# MSPBOIADV.net
KiCad netlist of a schematic drawn in EAGLE
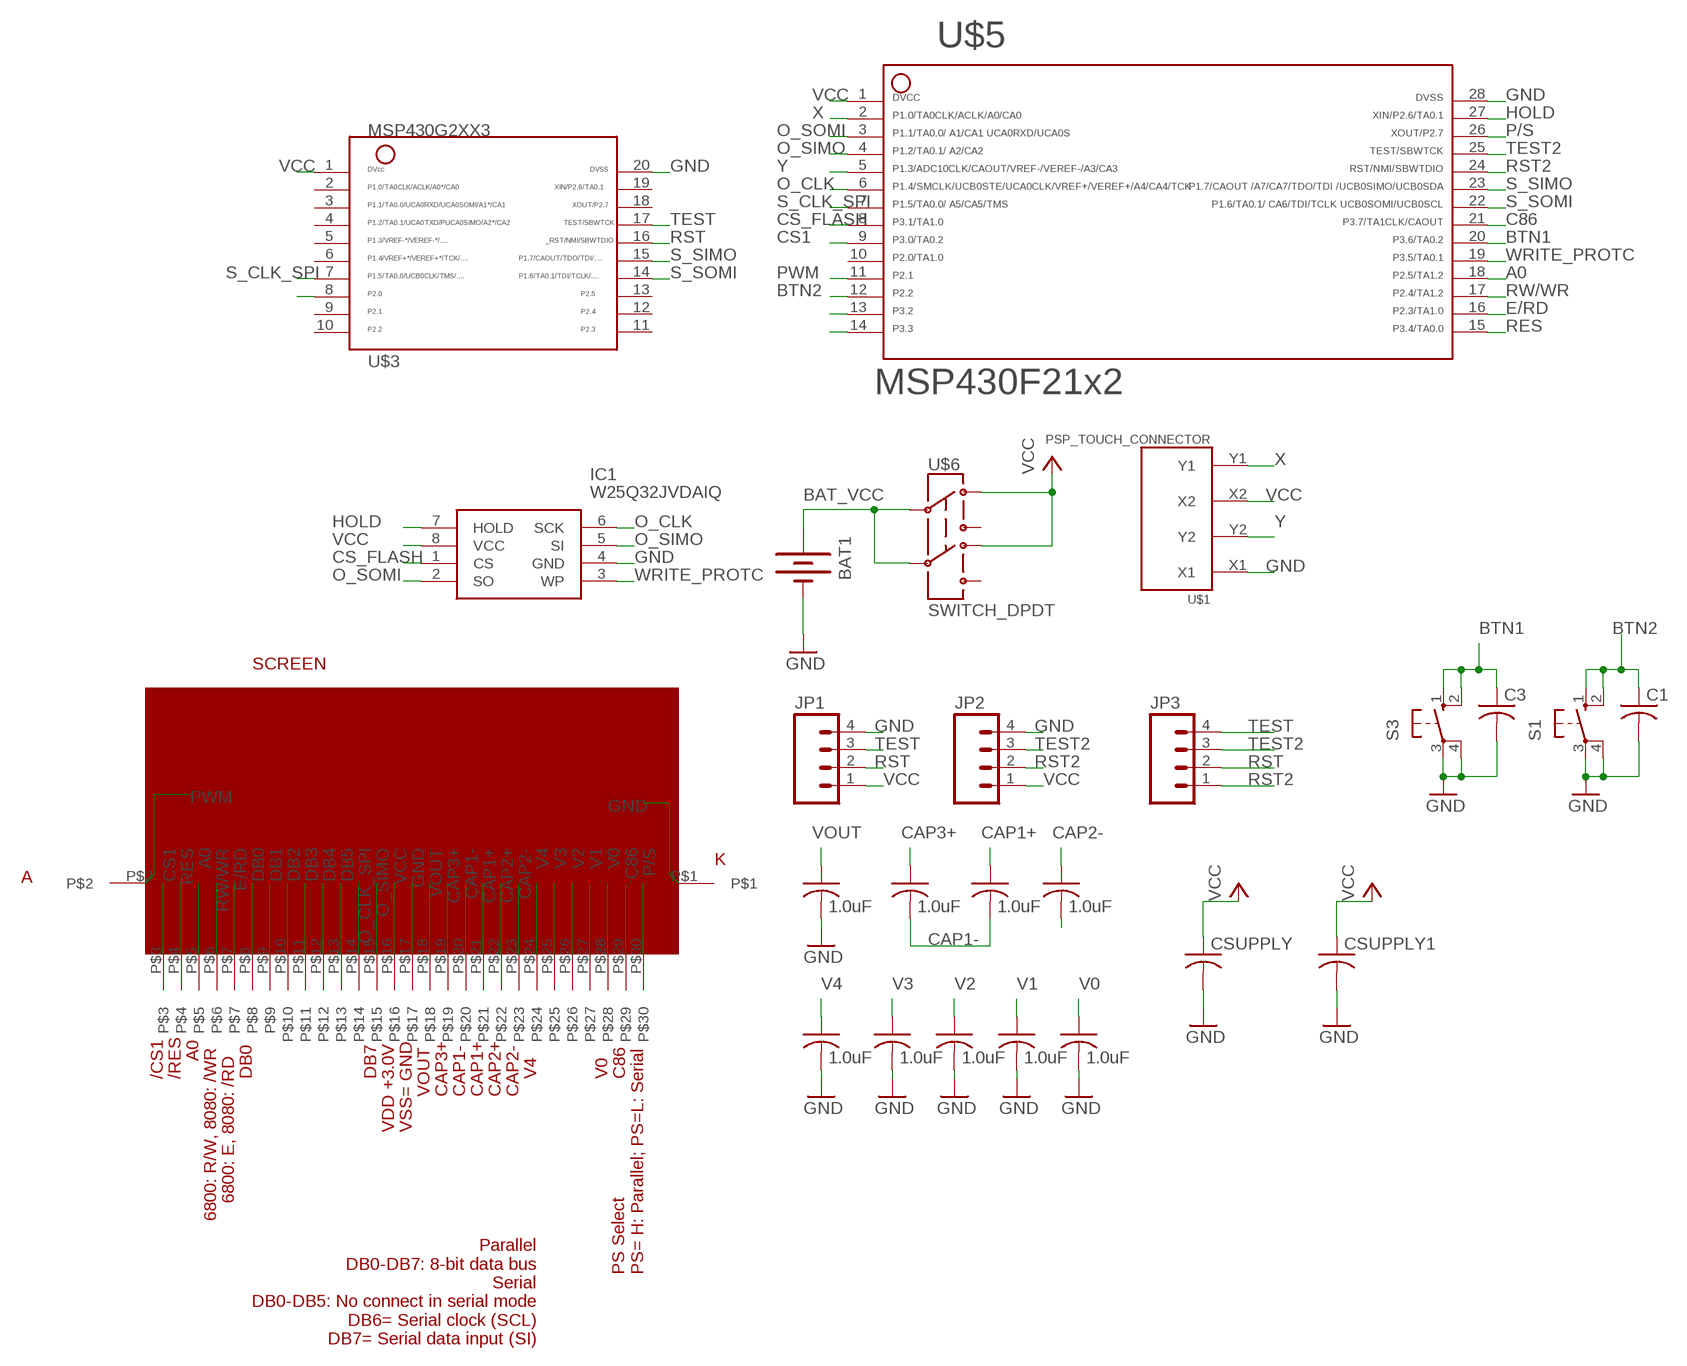
[diagram p0: schematic, sheet 1]

(export (version "E")
  (design (tool "Eeschema 10.0.6"))
  (components
    (comp (ref "1.0UF")
      (value "1.0uF")
      (footprint "eagle-import:C1206")
      (libsource (lib "eagle-import") (part "rcl_334_C-USC1206"))
    )
    (comp (ref "1.0UF1")
      (value "1.0uF")
      (footprint "eagle-import:C1206")
      (libsource (lib "eagle-import") (part "rcl_334_C-USC1206"))
    )
    (comp (ref "BAT1")
      (value "BATTERY")
      (footprint "eagle-import:BATTERY_PACK_2AA")
      (libsource (lib "eagle-import") (part "BATTERY"))
    )
    (comp (ref "C1")
      (value "C-USC1206")
      (footprint "eagle-import:C1206")
      (libsource (lib "eagle-import") (part "rcl_334_C-USC1206"))
    )
    (comp (ref "C3")
      (value "C-USC1206")
      (footprint "eagle-import:C1206")
      (libsource (lib "eagle-import") (part "rcl_334_C-USC1206"))
    )
    (comp (ref "CSUPPLY")
      (value "C-USC1206")
      (footprint "eagle-import:C1206")
      (libsource (lib "eagle-import") (part "C-USC1206"))
    )
    (comp (ref "CSUPPLY1")
      (value "C-USC1206")
      (footprint "eagle-import:C1206")
      (libsource (lib "eagle-import") (part "C-USC1206"))
    )
    (comp (ref "IC1")
      (value "W25Q32JVDAIQ")
      (footprint "eagle-import:DIP902W46P254L959H533Q8N")
      (libsource (lib "eagle-import") (part "W25Q32JVDAIQ"))
    )
    (comp (ref "JP1")
      (value "M04LOCK")
      (footprint "eagle-import:1X04_LOCK")
      (libsource (lib "eagle-import") (part "M04LOCK"))
    )
    (comp (ref "JP2")
      (value "M04LOCK")
      (footprint "eagle-import:1X04_LOCK")
      (libsource (lib "eagle-import") (part "M04LOCK"))
    )
    (comp (ref "JP3")
      (value "M04LOCK")
      (footprint "eagle-import:1X04_LOCK")
      (libsource (lib "eagle-import") (part "M04LOCK"))
    )
    (comp (ref "S1")
      (value "10-XX")
      (footprint "eagle-import:B3F-10XX")
      (fields (field (name "MPN") "B3F-1000"))
      (libsource (lib "eagle-import") (part "10-XX"))
    )
    (comp (ref "S3")
      (value "10-XX")
      (footprint "eagle-import:B3F-10XX")
      (fields (field (name "MPN") "B3F-1000"))
      (libsource (lib "eagle-import") (part "10-XX"))
    )
    (comp (ref "U$1")
      (value "PSP_TOUCH_CONNECTOR")
      (footprint "eagle-import:PSP_TOUCH_CONNECTOR")
      (libsource (lib "eagle-import") (part "PSP_TOUCH_CONNECTOR"))
    )
    (comp (ref "U$2")
      (value "SCREEN")
      (footprint "eagle-import:DISPLAY_128_64")
      (libsource (lib "eagle-import") (part "SCREEN"))
    )
    (comp (ref "U$3")
      (value "MSP430G2XX3TSSOP")
      (footprint "eagle-import:PW20")
      (libsource (lib "eagle-import") (part "MSP430G2XX3TSSOP"))
    )
    (comp (ref "U$5")
      (value "USETHIS")
      (footprint "eagle-import:PW28")
      (libsource (lib "eagle-import") (part "USETHIS"))
    )
    (comp (ref "U$6")
      (value "SWITCH_DPDT")
      (footprint "eagle-import:JS_DPDT_TH")
      (libsource (lib "eagle-import") (part "SWITCH_DPDT"))
    )
    (comp (ref "VOUTCAP")
      (value "1.0uF")
      (footprint "eagle-import:C1206")
      (libsource (lib "eagle-import") (part "rcl_334_C-USC1206"))
    )
    (comp (ref "VOUTCAP1")
      (value "1.0uF")
      (footprint "eagle-import:C1206")
      (libsource (lib "eagle-import") (part "rcl_334_C-USC1206"))
    )
    (comp (ref "VOUTCAP2")
      (value "1.0uF")
      (footprint "eagle-import:C1206")
      (libsource (lib "eagle-import") (part "rcl_334_C-USC1206"))
    )
    (comp (ref "VOUTCAP3")
      (value "1.0uF")
      (footprint "eagle-import:C1206")
      (libsource (lib "eagle-import") (part "rcl_334_C-USC1206"))
    )
    (comp (ref "VOUTCAP4")
      (value "1.0uF")
      (footprint "eagle-import:C1206")
      (libsource (lib "eagle-import") (part "rcl_334_C-USC1206"))
    )
    (comp (ref "VOUTCAP5")
      (value "1.0uF")
      (footprint "eagle-import:C1206")
      (libsource (lib "eagle-import") (part "rcl_334_C-USC1206"))
    )
    (comp (ref "VOUTCAP6")
      (value "1.0uF")
      (footprint "eagle-import:C1206")
      (libsource (lib "eagle-import") (part "rcl_334_C-USC1206"))
    )
  )
  (nets
    (net (code "1") (name "/A0") (class "Default")
      (node (ref "U$2") (pin "P$5") (pinfunction "P$5_P$5") (pintype "bidirectional"))
      (node (ref "U$5") (pin "18") (pinfunction "18_18") (pintype "bidirectional"))
    )
    (net (code "2") (name "/BAT_VCC") (class "Default")
      (node (ref "BAT1") (pin "3V") (pinfunction "+_3V") (pintype "power_in"))
      (node (ref "U$6") (pin "2") (pinfunction "2_2") (pintype "bidirectional"))
      (node (ref "U$6") (pin "5") (pinfunction "5_5") (pintype "bidirectional"))
    )
    (net (code "3") (name "/BTN1") (class "Default")
      (node (ref "C3") (pin "1") (pinfunction "1_1") (pintype "passive"))
      (node (ref "S3") (pin "1") (pinfunction "S_1") (pintype "passive"))
      (node (ref "S3") (pin "2") (pinfunction "S1_2") (pintype "passive"))
      (node (ref "U$5") (pin "20") (pinfunction "20_20") (pintype "bidirectional"))
    )
    (net (code "4") (name "/BTN2") (class "Default")
      (node (ref "C1") (pin "1") (pinfunction "1_1") (pintype "passive"))
      (node (ref "S1") (pin "1") (pinfunction "S_1") (pintype "passive"))
      (node (ref "S1") (pin "2") (pinfunction "S1_2") (pintype "passive"))
      (node (ref "U$5") (pin "12") (pinfunction "12_12") (pintype "bidirectional"))
    )
    (net (code "5") (name "/C86") (class "Default")
      (node (ref "U$2") (pin "P$29") (pinfunction "P$29_P$29") (pintype "bidirectional"))
      (node (ref "U$5") (pin "21") (pinfunction "21_21") (pintype "bidirectional"))
    )
    (net (code "6") (name "/CAP1+") (class "Default")
      (node (ref "1.0UF1") (pin "1") (pinfunction "1_1") (pintype "passive"))
      (node (ref "U$2") (pin "P$21") (pinfunction "P$21_P$21") (pintype "bidirectional"))
    )
    (net (code "7") (name "/CAP1-") (class "Default")
      (node (ref "1.0UF") (pin "2") (pinfunction "2_2") (pintype "passive"))
      (node (ref "1.0UF1") (pin "2") (pinfunction "2_2") (pintype "passive"))
      (node (ref "U$2") (pin "P$20") (pinfunction "P$20_P$20") (pintype "bidirectional"))
    )
    (net (code "8") (name "/CAP2+") (class "Default")
      (node (ref "U$2") (pin "P$22") (pinfunction "P$22_P$22") (pintype "bidirectional"))
      (node (ref "VOUTCAP1") (pin "2") (pinfunction "2_2") (pintype "passive"))
    )
    (net (code "9") (name "/CAP2-") (class "Default")
      (node (ref "U$2") (pin "P$23") (pinfunction "P$23_P$23") (pintype "bidirectional"))
      (node (ref "VOUTCAP1") (pin "1") (pinfunction "1_1") (pintype "passive"))
    )
    (net (code "10") (name "/CAP3+") (class "Default")
      (node (ref "1.0UF") (pin "1") (pinfunction "1_1") (pintype "passive"))
      (node (ref "U$2") (pin "P$19") (pinfunction "P$19_P$19") (pintype "bidirectional"))
    )
    (net (code "11") (name "/CS1") (class "Default")
      (node (ref "U$2") (pin "P$3") (pinfunction "P$3_P$3") (pintype "bidirectional"))
      (node (ref "U$5") (pin "9") (pinfunction "9_9") (pintype "bidirectional"))
    )
    (net (code "12") (name "/CS_FLASH") (class "Default")
      (node (ref "IC1") (pin "1") (pinfunction "CS_1") (pintype "bidirectional"))
      (node (ref "U$5") (pin "8") (pinfunction "8_8") (pintype "bidirectional"))
    )
    (net (code "13") (name "/DB0") (class "Default")
      (node (ref "U$2") (pin "P$8") (pinfunction "P$8_P$8") (pintype "bidirectional"))
    )
    (net (code "14") (name "/DB1") (class "Default")
      (node (ref "U$2") (pin "P$9") (pinfunction "P$9_P$9") (pintype "bidirectional"))
    )
    (net (code "15") (name "/DB2") (class "Default")
      (node (ref "U$2") (pin "P$10") (pinfunction "P$10_P$10") (pintype "bidirectional"))
    )
    (net (code "16") (name "/DB3") (class "Default")
      (node (ref "U$2") (pin "P$11") (pinfunction "P$11_P$11") (pintype "bidirectional"))
    )
    (net (code "17") (name "/DB4") (class "Default")
      (node (ref "U$2") (pin "P$12") (pinfunction "P$12_P$12") (pintype "bidirectional"))
    )
    (net (code "18") (name "/DB5") (class "Default")
      (node (ref "U$2") (pin "P$13") (pinfunction "P$13_P$13") (pintype "bidirectional"))
    )
    (net (code "19") (name "/E{slash}RD") (class "Default")
      (node (ref "U$2") (pin "P$7") (pinfunction "P$7_P$7") (pintype "bidirectional"))
      (node (ref "U$5") (pin "16") (pinfunction "16_16") (pintype "bidirectional"))
    )
    (net (code "20") (name "/HOLD") (class "Default")
      (node (ref "IC1") (pin "7") (pinfunction "HOLD_7") (pintype "input"))
      (node (ref "U$5") (pin "27") (pinfunction "27_27") (pintype "bidirectional"))
    )
    (net (code "21") (name "/O_CLK") (class "Default")
      (node (ref "IC1") (pin "6") (pinfunction "SCK_6") (pintype "power_in"))
      (node (ref "U$5") (pin "6") (pinfunction "6_6") (pintype "bidirectional"))
    )
    (net (code "22") (name "/O_CLK_SPI") (class "Default")
      (node (ref "U$2") (pin "P$14") (pinfunction "P$14_P$14") (pintype "bidirectional"))
    )
    (net (code "23") (name "/O_SIMO") (class "Default")
      (node (ref "IC1") (pin "5") (pinfunction "SI_5") (pintype "bidirectional"))
      (node (ref "U$2") (pin "P$15") (pinfunction "P$15_P$15") (pintype "bidirectional"))
      (node (ref "U$5") (pin "4") (pinfunction "4_4") (pintype "bidirectional"))
    )
    (net (code "24") (name "/O_SOMI") (class "Default")
      (node (ref "IC1") (pin "2") (pinfunction "SO_2") (pintype "power_in"))
      (node (ref "U$5") (pin "3") (pinfunction "3_3") (pintype "bidirectional"))
    )
    (net (code "25") (name "/PWM") (class "Default")
      (node (ref "U$2") (pin "P$2") (pinfunction "P$2_P$2") (pintype "bidirectional"))
      (node (ref "U$5") (pin "11") (pinfunction "11_11") (pintype "bidirectional"))
    )
    (net (code "26") (name "/P{slash}S") (class "Default")
      (node (ref "U$2") (pin "P$30") (pinfunction "P$30_P$30") (pintype "bidirectional"))
      (node (ref "U$5") (pin "26") (pinfunction "26_26") (pintype "bidirectional"))
    )
    (net (code "27") (name "/RES") (class "Default")
      (node (ref "U$2") (pin "P$4") (pinfunction "P$4_P$4") (pintype "bidirectional"))
      (node (ref "U$5") (pin "15") (pinfunction "15_15") (pintype "bidirectional"))
    )
    (net (code "28") (name "/RST") (class "Default")
      (node (ref "JP1") (pin "2") (pinfunction "2_2") (pintype "passive"))
      (node (ref "JP3") (pin "2") (pinfunction "2_2") (pintype "passive"))
      (node (ref "U$3") (pin "16") (pinfunction "16_16") (pintype "bidirectional"))
    )
    (net (code "29") (name "/RST2") (class "Default")
      (node (ref "JP2") (pin "2") (pinfunction "2_2") (pintype "passive"))
      (node (ref "JP3") (pin "1") (pinfunction "1_1") (pintype "passive"))
      (node (ref "U$5") (pin "24") (pinfunction "24_24") (pintype "bidirectional"))
    )
    (net (code "30") (name "/RW{slash}WR") (class "Default")
      (node (ref "U$2") (pin "P$6") (pinfunction "P$6_P$6") (pintype "bidirectional"))
      (node (ref "U$5") (pin "17") (pinfunction "17_17") (pintype "bidirectional"))
    )
    (net (code "31") (name "/S_CLK_SPI") (class "Default")
      (node (ref "U$3") (pin "7") (pinfunction "7_7") (pintype "bidirectional"))
      (node (ref "U$5") (pin "7") (pinfunction "7_7") (pintype "input"))
    )
    (net (code "32") (name "/S_SIMO") (class "Default")
      (node (ref "U$3") (pin "15") (pinfunction "15_15") (pintype "bidirectional"))
      (node (ref "U$5") (pin "23") (pinfunction "23_23") (pintype "bidirectional"))
    )
    (net (code "33") (name "/S_SOMI") (class "Default")
      (node (ref "U$3") (pin "14") (pinfunction "14_14") (pintype "bidirectional"))
      (node (ref "U$5") (pin "22") (pinfunction "22_22") (pintype "bidirectional"))
    )
    (net (code "34") (name "/TEST") (class "Default")
      (node (ref "JP1") (pin "3") (pinfunction "3_3") (pintype "passive"))
      (node (ref "JP3") (pin "4") (pinfunction "4_4") (pintype "passive"))
      (node (ref "U$3") (pin "17") (pinfunction "17_17") (pintype "bidirectional"))
    )
    (net (code "35") (name "/TEST2") (class "Default")
      (node (ref "JP2") (pin "3") (pinfunction "3_3") (pintype "passive"))
      (node (ref "JP3") (pin "3") (pinfunction "3_3") (pintype "passive"))
      (node (ref "U$5") (pin "25") (pinfunction "25_25") (pintype "bidirectional"))
    )
    (net (code "36") (name "/V0") (class "Default")
      (node (ref "U$2") (pin "P$28") (pinfunction "P$28_P$28") (pintype "bidirectional"))
      (node (ref "VOUTCAP6") (pin "1") (pinfunction "1_1") (pintype "passive"))
    )
    (net (code "37") (name "/V1") (class "Default")
      (node (ref "U$2") (pin "P$27") (pinfunction "P$27_P$27") (pintype "bidirectional"))
      (node (ref "VOUTCAP5") (pin "1") (pinfunction "1_1") (pintype "passive"))
    )
    (net (code "38") (name "/V2") (class "Default")
      (node (ref "U$2") (pin "P$26") (pinfunction "P$26_P$26") (pintype "bidirectional"))
      (node (ref "VOUTCAP4") (pin "1") (pinfunction "1_1") (pintype "passive"))
    )
    (net (code "39") (name "/V3") (class "Default")
      (node (ref "U$2") (pin "P$25") (pinfunction "P$25_P$25") (pintype "bidirectional"))
      (node (ref "VOUTCAP3") (pin "1") (pinfunction "1_1") (pintype "passive"))
    )
    (net (code "40") (name "/V4") (class "Default")
      (node (ref "U$2") (pin "P$24") (pinfunction "P$24_P$24") (pintype "bidirectional"))
      (node (ref "VOUTCAP2") (pin "1") (pinfunction "1_1") (pintype "passive"))
    )
    (net (code "41") (name "/VOUT") (class "Default")
      (node (ref "U$2") (pin "P$18") (pinfunction "P$18_P$18") (pintype "bidirectional"))
      (node (ref "VOUTCAP") (pin "1") (pinfunction "1_1") (pintype "passive"))
    )
    (net (code "42") (name "/WRITE_PROTC") (class "Default")
      (node (ref "IC1") (pin "3") (pinfunction "WP_3") (pintype "bidirectional"))
      (node (ref "U$5") (pin "19") (pinfunction "19_19") (pintype "bidirectional"))
    )
    (net (code "43") (name "/X") (class "Default")
      (node (ref "U$1") (pin "Y1") (pinfunction "Y1_Y1") (pintype "bidirectional"))
      (node (ref "U$5") (pin "2") (pinfunction "2_2") (pintype "bidirectional"))
    )
    (net (code "44") (name "/Y") (class "Default")
      (node (ref "U$1") (pin "Y2") (pinfunction "Y2_Y2") (pintype "bidirectional"))
      (node (ref "U$5") (pin "5") (pinfunction "5_5") (pintype "bidirectional"))
    )
    (net (code "45") (name "GND") (class "Default")
      (node (ref "BAT1") (pin "GND") (pinfunction "-_GND") (pintype "power_in"))
      (node (ref "C1") (pin "2") (pinfunction "2_2") (pintype "passive"))
      (node (ref "C3") (pin "2") (pinfunction "2_2") (pintype "passive"))
      (node (ref "CSUPPLY") (pin "2") (pinfunction "2_2") (pintype "passive"))
      (node (ref "CSUPPLY1") (pin "2") (pinfunction "2_2") (pintype "passive"))
      (node (ref "IC1") (pin "4") (pinfunction "GND_4") (pintype "input"))
      (node (ref "JP1") (pin "4") (pinfunction "4_4") (pintype "passive"))
      (node (ref "JP2") (pin "4") (pinfunction "4_4") (pintype "passive"))
      (node (ref "S1") (pin "3") (pinfunction "P_3") (pintype "passive"))
      (node (ref "S1") (pin "4") (pinfunction "P1_4") (pintype "passive"))
      (node (ref "S3") (pin "3") (pinfunction "P_3") (pintype "passive"))
      (node (ref "S3") (pin "4") (pinfunction "P1_4") (pintype "passive"))
      (node (ref "U$1") (pin "X1") (pinfunction "X1_X1") (pintype "bidirectional"))
      (node (ref "U$2") (pin "P$1") (pinfunction "P$1_P$1") (pintype "bidirectional"))
      (node (ref "U$2") (pin "P$17") (pinfunction "P$17_P$17") (pintype "bidirectional"))
      (node (ref "U$3") (pin "20") (pinfunction "20_20") (pintype "bidirectional"))
      (node (ref "U$5") (pin "28") (pinfunction "28_28") (pintype "bidirectional"))
      (node (ref "VOUTCAP") (pin "2") (pinfunction "2_2") (pintype "passive"))
      (node (ref "VOUTCAP2") (pin "2") (pinfunction "2_2") (pintype "passive"))
      (node (ref "VOUTCAP3") (pin "2") (pinfunction "2_2") (pintype "passive"))
      (node (ref "VOUTCAP4") (pin "2") (pinfunction "2_2") (pintype "passive"))
      (node (ref "VOUTCAP5") (pin "2") (pinfunction "2_2") (pintype "passive"))
      (node (ref "VOUTCAP6") (pin "2") (pinfunction "2_2") (pintype "passive"))
    )
    (net (code "46") (name "VCC") (class "Default")
      (node (ref "CSUPPLY") (pin "1") (pinfunction "1_1") (pintype "passive"))
      (node (ref "CSUPPLY1") (pin "1") (pinfunction "1_1") (pintype "passive"))
      (node (ref "IC1") (pin "8") (pinfunction "VCC_8") (pintype "bidirectional"))
      (node (ref "JP1") (pin "1") (pinfunction "1_1") (pintype "passive"))
      (node (ref "JP2") (pin "1") (pinfunction "1_1") (pintype "passive"))
      (node (ref "U$1") (pin "X2") (pinfunction "X2_X2") (pintype "bidirectional"))
      (node (ref "U$2") (pin "P$16") (pinfunction "P$16_P$16") (pintype "bidirectional"))
      (node (ref "U$3") (pin "1") (pinfunction "1_1") (pintype "bidirectional"))
      (node (ref "U$5") (pin "1") (pinfunction "1_1") (pintype "power_in"))
      (node (ref "U$6") (pin "1") (pinfunction "1_1") (pintype "bidirectional"))
      (node (ref "U$6") (pin "4") (pinfunction "4_4") (pintype "bidirectional"))
    )
    (net (code "47") (name "unconnected-(U$3-Pad2)") (class "Default")
      (node (ref "U$3") (pin "2") (pinfunction "2_2") (pintype "bidirectional"))
    )
    (net (code "48") (name "unconnected-(U$3-Pad3)") (class "Default")
      (node (ref "U$3") (pin "3") (pinfunction "3_3") (pintype "bidirectional"))
    )
    (net (code "49") (name "unconnected-(U$3-Pad4)") (class "Default")
      (node (ref "U$3") (pin "4") (pinfunction "4_4") (pintype "bidirectional"))
    )
    (net (code "50") (name "unconnected-(U$3-Pad5)") (class "Default")
      (node (ref "U$3") (pin "5") (pinfunction "5_5") (pintype "bidirectional"))
    )
    (net (code "51") (name "unconnected-(U$3-Pad6)") (class "Default")
      (node (ref "U$3") (pin "6") (pinfunction "6_6") (pintype "bidirectional"))
    )
    (net (code "52") (name "unconnected-(U$3-Pad8)") (class "Default")
      (node (ref "U$3") (pin "8") (pinfunction "8_8") (pintype "bidirectional"))
    )
    (net (code "53") (name "unconnected-(U$3-Pad9)") (class "Default")
      (node (ref "U$3") (pin "9") (pinfunction "9_9") (pintype "bidirectional"))
    )
    (net (code "54") (name "unconnected-(U$3-Pad10)") (class "Default")
      (node (ref "U$3") (pin "10") (pinfunction "10_10") (pintype "bidirectional"))
    )
    (net (code "55") (name "unconnected-(U$3-Pad11)") (class "Default")
      (node (ref "U$3") (pin "11") (pinfunction "11_11") (pintype "bidirectional"))
    )
    (net (code "56") (name "unconnected-(U$3-Pad12)") (class "Default")
      (node (ref "U$3") (pin "12") (pinfunction "12_12") (pintype "bidirectional"))
    )
    (net (code "57") (name "unconnected-(U$3-Pad13)") (class "Default")
      (node (ref "U$3") (pin "13") (pinfunction "13_13") (pintype "bidirectional"))
    )
    (net (code "58") (name "unconnected-(U$3-Pad18)") (class "Default")
      (node (ref "U$3") (pin "18") (pinfunction "18_18") (pintype "bidirectional"))
    )
    (net (code "59") (name "unconnected-(U$3-Pad19)") (class "Default")
      (node (ref "U$3") (pin "19") (pinfunction "19_19") (pintype "bidirectional"))
    )
    (net (code "60") (name "unconnected-(U$5-Pad10)") (class "Default")
      (node (ref "U$5") (pin "10") (pinfunction "10_10") (pintype "bidirectional"))
    )
    (net (code "61") (name "unconnected-(U$5-Pad13)") (class "Default")
      (node (ref "U$5") (pin "13") (pinfunction "13_13") (pintype "bidirectional"))
    )
    (net (code "62") (name "unconnected-(U$5-Pad14)") (class "Default")
      (node (ref "U$5") (pin "14") (pinfunction "14_14") (pintype "bidirectional"))
    )
    (net (code "63") (name "unconnected-(U$6-Pad3)") (class "Default")
      (node (ref "U$6") (pin "3") (pinfunction "3_3") (pintype "bidirectional"))
    )
    (net (code "64") (name "unconnected-(U$6-Pad6)") (class "Default")
      (node (ref "U$6") (pin "6") (pinfunction "6_6") (pintype "bidirectional"))
    )
  )
)
